# PCB_MINI_FB_ACS_V1.net
KiCad netlist of a schematic drawn in EasyEDA
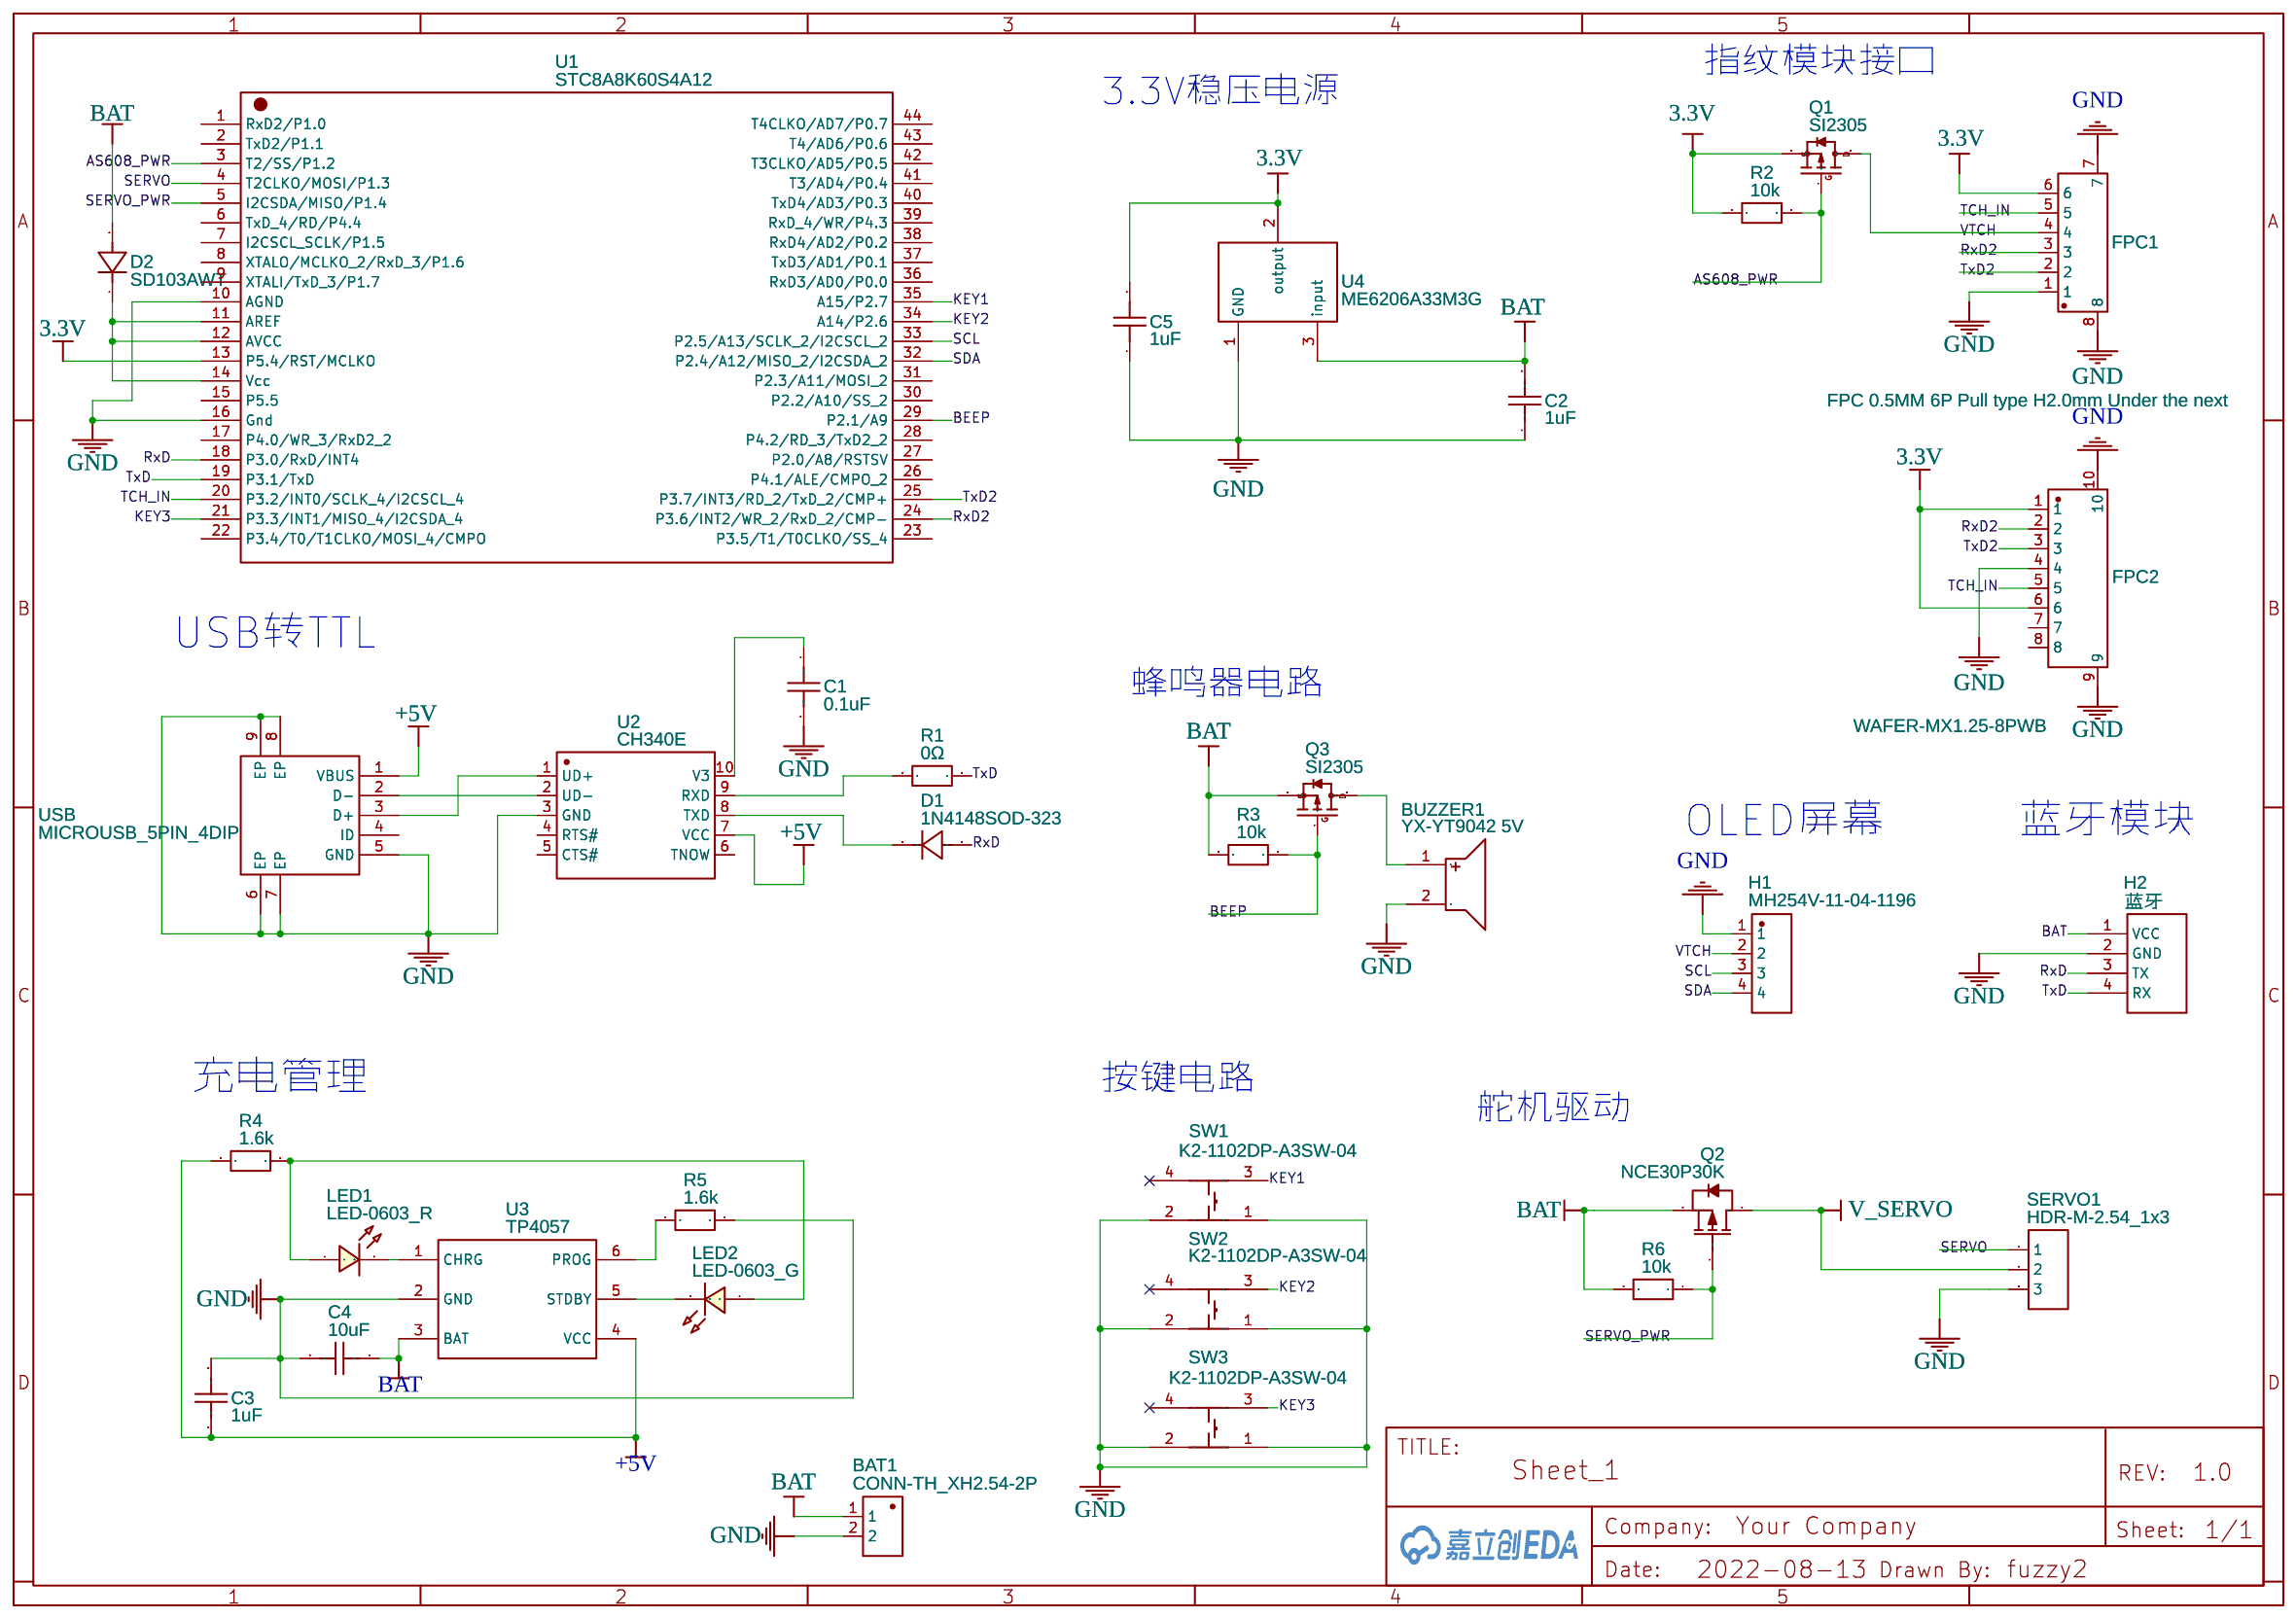
[diagram p0: schematic sheet]

(export (version "E")
  (design (tool "Eeschema 10.0.6"))
  (components
    (comp (ref "BAT1")
      (value "CONN-TH_XH2.54-2P")
      (fields
        (field (name "BOM_Manufacturer Part") "HX25037-2A")
        (field (name "BOM_Supplier Part") "C9900012767")
      )
      (libsource (lib "") (part "CONN-TH_XH2.54-2P"))
    )
    (comp (ref "BUZZER1")
      (value "YX-YT9042 5V")
      (fields
        (field (name "BOM_Manufacturer Part") "YX-YT9042 5v")
        (field (name "BOM_Supplier Part") "C781848")
      )
      (libsource (lib "") (part "YX-YT9042 5V"))
    )
    (comp (ref "C1")
      (value "0.1uF")
      (fields
        (field (name "BOM_Manufacturer Part") "0603BB104K500NGT")
        (field (name "BOM_Supplier Part") "C2168571")
      )
      (libsource (lib "") (part "0603BB104K500NGT"))
    )
    (comp (ref "C2")
      (value "1uF")
      (fields
        (field (name "BOM_Manufacturer Part") "CL10A105KP8NNWC")
        (field (name "BOM_Supplier Part") "C307456")
      )
      (libsource (lib "") (part "CL10A105KP8NNWC"))
    )
    (comp (ref "C3")
      (value "1uF")
      (fields
        (field (name "BOM_Manufacturer Part") "CL10A105KP8NNWC")
        (field (name "BOM_Supplier Part") "C307456")
      )
      (libsource (lib "") (part "CL10A105KP8NNWC"))
    )
    (comp (ref "C4")
      (value "10uF")
      (fields
        (field (name "BOM_Manufacturer Part") "CL10A106MA8NRNC")
        (field (name "BOM_Supplier Part") "C96446")
      )
      (libsource (lib "") (part "CL10A106MA8NRNC"))
    )
    (comp (ref "C5")
      (value "1uF")
      (fields
        (field (name "BOM_Manufacturer Part") "CL10A105KP8NNWC")
        (field (name "BOM_Supplier Part") "C307456")
      )
      (libsource (lib "") (part "CL10A105KP8NNWC"))
    )
    (comp (ref "D1")
      (value "1N4148SOD-323")
      (fields (field (name "BOM_Supplier Part") "C2972761"))
      (libsource (lib "") (part "1N4148SOD-323"))
    )
    (comp (ref "D2")
      (value "SD103AWT")
      (fields (field (name "BOM_Supplier Part") "C840750"))
      (libsource (lib "") (part "SD103AWT"))
    )
    (comp (ref "FPC1")
      (value "FPC 0.5MM 6P Pull type H2.0mm Under the next")
      (fields (field (name "BOM_Supplier Part") "C11048"))
      (libsource (lib "") (part "FPC 0.5MM 6P Pull type H2.0mm Under the next"))
    )
    (comp (ref "FPC2")
      (value "WAFER-MX1.25-8PWB")
      (fields (field (name "BOM_Supplier Part") "C3029365"))
      (libsource (lib "") (part "WAFER-MX1.25-8PWB"))
    )
    (comp (ref "H1")
      (value "MH254V-11-04-1196")
      (fields (field (name "BOM_Supplier Part") "C3015083"))
      (libsource (lib "") (part "MH254V-11-04-1196"))
    )
    (comp (ref "H2")
      (value "蓝牙")
      (fields
        (field (name "BOM_Manufacturer Part") "220S-1*4P H=8.5MM Ytype Gold-plated")
        (field (name "BOM_Supplier Part") "C124413")
      )
      (libsource (lib "") (part "蓝牙"))
    )
    (comp (ref "LED1")
      (value "LED-0603_R")
      (fields
        (field (name "BOM_Manufacturer Part") "19-217/R6C-AL1M2VY/3T")
        (field (name "BOM_Supplier Part") "C72044")
      )
      (libsource (lib "") (part "LED-0603_R"))
    )
    (comp (ref "LED2")
      (value "LED-0603_G")
      (fields
        (field (name "BOM_Manufacturer Part") "19-217/GHC-YR1S2/3T")
        (field (name "BOM_Supplier Part") "C72043")
      )
      (libsource (lib "") (part "LED-0603_G"))
    )
    (comp (ref "Q1")
      (value "SI2305")
      (fields (field (name "BOM_Supplier Part") "C181088"))
      (libsource (lib "") (part "SI2305"))
    )
    (comp (ref "Q2")
      (value "NCE30P30K")
      (fields (field (name "BOM_Supplier Part") "C130106"))
      (libsource (lib "") (part "NCE30P30K"))
    )
    (comp (ref "Q3")
      (value "SI2305")
      (fields (field (name "BOM_Supplier Part") "C181088"))
      (libsource (lib "") (part "SI2305"))
    )
    (comp (ref "R1")
      (value "0Ω")
      (fields
        (field (name "BOM_Manufacturer Part") "CSRF0603FT2L50")
        (field (name "BOM_Supplier Part") "C106974")
      )
      (libsource (lib "") (part "CSRF0603FT2L50"))
    )
    (comp (ref "R2")
      (value "10k")
      (fields
        (field (name "BOM_Manufacturer Part") "0603WAF510KT5E")
        (field (name "BOM_Supplier Part") "C25197")
      )
      (libsource (lib "") (part "R_0603_EU"))
    )
    (comp (ref "R3")
      (value "10k")
      (fields
        (field (name "BOM_Manufacturer Part") "0603WAF510KT5E")
        (field (name "BOM_Supplier Part") "C25197")
      )
      (libsource (lib "") (part "R_0603_EU"))
    )
    (comp (ref "R4")
      (value "1.6k")
      (fields
        (field (name "BOM_Manufacturer Part") "RMC060331.6K1%N")
        (field (name "BOM_Supplier Part") "C325743")
      )
      (libsource (lib "") (part "R_0603_EU"))
    )
    (comp (ref "R5")
      (value "1.6k")
      (fields
        (field (name "BOM_Manufacturer Part") "RMC060331.6K1%N")
        (field (name "BOM_Supplier Part") "C325743")
      )
      (libsource (lib "") (part "R_0603_EU"))
    )
    (comp (ref "R6")
      (value "10k")
      (fields
        (field (name "BOM_Manufacturer Part") "0603WAF510KT5E")
        (field (name "BOM_Supplier Part") "C25197")
      )
      (libsource (lib "") (part "R_0603_EU"))
    )
    (comp (ref "SERVO1")
      (value "HDR-M-2.54_1x3")
      (fields (field (name "BOM_Supplier Part") "C180248"))
      (libsource (lib "") (part "HDR-M-2.54_1x3"))
    )
    (comp (ref "SW1")
      (value "K2-1102DP-A3SW-04")
      (fields (field (name "BOM_Supplier Part") "C136685"))
      (libsource (lib "") (part "K2-1102DP-A3SW-04"))
    )
    (comp (ref "SW2")
      (value "K2-1102DP-A3SW-04")
      (fields (field (name "BOM_Supplier Part") "C136685"))
      (libsource (lib "") (part "K2-1102DP-A3SW-04"))
    )
    (comp (ref "SW3")
      (value "K2-1102DP-A3SW-04")
      (fields (field (name "BOM_Supplier Part") "C136685"))
      (libsource (lib "") (part "K2-1102DP-A3SW-04"))
    )
    (comp (ref "U1")
      (value "STC8A8K60S4A12")
      (fields (field (name "BOM_Supplier Part") "C98240"))
      (libsource (lib "") (part "STC8A8K60S4A12"))
    )
    (comp (ref "U2")
      (value "CH340E")
      (fields (field (name "BOM_Supplier Part") "C99652"))
      (libsource (lib "") (part "CH340E"))
    )
    (comp (ref "U3")
      (value "TP4057")
      (fields (field (name "BOM_Supplier Part") "C12044"))
      (libsource (lib "") (part "TP4057"))
    )
    (comp (ref "U4")
      (value "ME6206A33M3G")
      (fields
        (field (name "BOM_Manufacturer Part") "LN6206P332MR-G")
        (field (name "BOM_Supplier Part") "C141407")
      )
      (libsource (lib "") (part "ME6206A33M3G"))
    )
    (comp (ref "USB")
      (value "MICROUSB_5PIN_4DIP")
      (fields (field (name "BOM_Supplier Part") "C9900010529"))
      (libsource (lib "") (part "MICROUSB_5PIN_4DIP"))
    )
  )
  (nets
    (net (code "1") (name "+5V") (class "Default")
      (node (ref "C3") (pin "1") (pinfunction "1_1") (pintype "unspecified"))
      (node (ref "R4") (pin "2") (pinfunction "2_2") (pintype "unspecified"))
      (node (ref "U2") (pin "7") (pinfunction "VCC_7") (pintype "unspecified"))
      (node (ref "U3") (pin "4") (pinfunction "VCC_4") (pintype "unspecified"))
      (node (ref "USB") (pin "1") (pinfunction "VBUS_1") (pintype "unspecified"))
    )
    (net (code "2") (name "/AS608_PWR") (class "Default")
      (node (ref "Q1") (pin "1") (pinfunction "G_1") (pintype "unspecified"))
      (node (ref "R2") (pin "1") (pinfunction "1_1") (pintype "unspecified"))
      (node (ref "U1") (pin "3") (pinfunction "T2/SS/P1.2_3") (pintype "unspecified"))
    )
    (net (code "3") (name "/BEEP") (class "Default")
      (node (ref "Q3") (pin "1") (pinfunction "G_1") (pintype "unspecified"))
      (node (ref "R3") (pin "1") (pinfunction "1_1") (pintype "unspecified"))
      (node (ref "U1") (pin "29") (pinfunction "P2.1/A9_29") (pintype "unspecified"))
    )
    (net (code "4") (name "/KEY1") (class "Default")
      (node (ref "SW1") (pin "3") (pinfunction "3_3") (pintype "unspecified"))
      (node (ref "U1") (pin "35") (pinfunction "A15/P2.7_35") (pintype "unspecified"))
    )
    (net (code "5") (name "/KEY2") (class "Default")
      (node (ref "SW2") (pin "3") (pinfunction "3_3") (pintype "unspecified"))
      (node (ref "U1") (pin "34") (pinfunction "A14/P2.6_34") (pintype "unspecified"))
    )
    (net (code "6") (name "/KEY3") (class "Default")
      (node (ref "SW3") (pin "3") (pinfunction "3_3") (pintype "unspecified"))
      (node (ref "U1") (pin "21") (pinfunction "P3.3/INT1/MISO_4/I2CSDA_4_21") (pintype "unspecified"))
    )
    (net (code "7") (name "/RxD") (class "Default")
      (node (ref "D1") (pin "2") (pinfunction "A_2") (pintype "unspecified"))
      (node (ref "H2") (pin "3") (pinfunction "TX_3") (pintype "unspecified"))
      (node (ref "U1") (pin "18") (pinfunction "P3.0/RxD/INT4_18") (pintype "unspecified"))
    )
    (net (code "8") (name "/RxD2") (class "Default")
      (node (ref "FPC1") (pin "3") (pinfunction "3_3") (pintype "unspecified"))
      (node (ref "FPC2") (pin "2") (pinfunction "2_2") (pintype "unspecified"))
      (node (ref "U1") (pin "24") (pinfunction "P3.6/INT2/WR_2/RxD_2/CMP-_24") (pintype "unspecified"))
    )
    (net (code "9") (name "/SCL") (class "Default")
      (node (ref "H1") (pin "3") (pinfunction "3_3") (pintype "unspecified"))
      (node (ref "U1") (pin "33") (pinfunction "P2.5/A13/SCLK_2/I2CSCL_2_33") (pintype "unspecified"))
    )
    (net (code "10") (name "/SDA") (class "Default")
      (node (ref "H1") (pin "4") (pinfunction "4_4") (pintype "unspecified"))
      (node (ref "U1") (pin "32") (pinfunction "P2.4/A12/MISO_2/I2CSDA_2_32") (pintype "unspecified"))
    )
    (net (code "11") (name "/SERVO") (class "Default")
      (node (ref "SERVO1") (pin "1") (pinfunction "1_1") (pintype "input"))
      (node (ref "U1") (pin "4") (pinfunction "T2CLKO/MOSI/P1.3_4") (pintype "unspecified"))
    )
    (net (code "12") (name "/SERVO_PWR") (class "Default")
      (node (ref "Q2") (pin "1") (pinfunction "G_1") (pintype "unspecified"))
      (node (ref "R6") (pin "1") (pinfunction "1_1") (pintype "unspecified"))
      (node (ref "U1") (pin "5") (pinfunction "I2CSDA/MISO/P1.4_5") (pintype "unspecified"))
    )
    (net (code "13") (name "/TCH_IN") (class "Default")
      (node (ref "FPC1") (pin "5") (pinfunction "5_5") (pintype "unspecified"))
      (node (ref "FPC2") (pin "5") (pinfunction "5_5") (pintype "unspecified"))
      (node (ref "U1") (pin "20") (pinfunction "P3.2/INT0/SCLK_4/I2CSCL_4_20") (pintype "unspecified"))
    )
    (net (code "14") (name "/TxD") (class "Default")
      (node (ref "H2") (pin "4") (pinfunction "RX_4") (pintype "unspecified"))
      (node (ref "R1") (pin "2") (pinfunction "2_2") (pintype "unspecified"))
      (node (ref "U1") (pin "19") (pinfunction "P3.1/TxD_19") (pintype "unspecified"))
    )
    (net (code "15") (name "/TxD2") (class "Default")
      (node (ref "FPC1") (pin "2") (pinfunction "2_2") (pintype "unspecified"))
      (node (ref "FPC2") (pin "3") (pinfunction "3_3") (pintype "unspecified"))
      (node (ref "U1") (pin "25") (pinfunction "P3.7/INT3/RD_2/TxD_2/CMP+_25") (pintype "unspecified"))
    )
    (net (code "16") (name "/VTCH") (class "Default")
      (node (ref "FPC1") (pin "4") (pinfunction "4_4") (pintype "unspecified"))
      (node (ref "H1") (pin "2") (pinfunction "2_2") (pintype "unspecified"))
      (node (ref "Q1") (pin "3") (pinfunction "D_3") (pintype "unspecified"))
    )
    (net (code "17") (name "3.3V") (class "Default")
      (node (ref "C5") (pin "2") (pinfunction "2_2") (pintype "unspecified"))
      (node (ref "FPC1") (pin "6") (pinfunction "6_6") (pintype "unspecified"))
      (node (ref "FPC2") (pin "1") (pinfunction "1_1") (pintype "unspecified"))
      (node (ref "FPC2") (pin "6") (pinfunction "6_6") (pintype "unspecified"))
      (node (ref "Q1") (pin "2") (pinfunction "S_2") (pintype "unspecified"))
      (node (ref "R2") (pin "2") (pinfunction "2_2") (pintype "unspecified"))
      (node (ref "U1") (pin "13") (pinfunction "P5.4/RST/MCLKO_13") (pintype "unspecified"))
      (node (ref "U4") (pin "2") (pinfunction "output_2") (pintype "unspecified"))
    )
    (net (code "18") (name "BAT") (class "Default")
      (node (ref "BAT1") (pin "1") (pinfunction "1_1") (pintype "unspecified"))
      (node (ref "C2") (pin "2") (pinfunction "2_2") (pintype "unspecified"))
      (node (ref "C4") (pin "2") (pinfunction "2_2") (pintype "unspecified"))
      (node (ref "D2") (pin "2") (pinfunction "A_2") (pintype "unspecified"))
      (node (ref "H2") (pin "1") (pinfunction "VCC_1") (pintype "unspecified"))
      (node (ref "Q2") (pin "3") (pinfunction "S_3") (pintype "unspecified"))
      (node (ref "Q3") (pin "2") (pinfunction "S_2") (pintype "unspecified"))
      (node (ref "R3") (pin "2") (pinfunction "2_2") (pintype "unspecified"))
      (node (ref "R6") (pin "2") (pinfunction "2_2") (pintype "unspecified"))
      (node (ref "U3") (pin "3") (pinfunction "BAT_3") (pintype "unspecified"))
      (node (ref "U4") (pin "3") (pinfunction "input_3") (pintype "unspecified"))
    )
    (net (code "19") (name "GND") (class "Default")
      (node (ref "BAT1") (pin "2") (pinfunction "2_2") (pintype "unspecified"))
      (node (ref "BUZZER1") (pin "2") (pinfunction "2_2") (pintype "unspecified"))
      (node (ref "C1") (pin "2") (pinfunction "2_2") (pintype "unspecified"))
      (node (ref "C2") (pin "1") (pinfunction "1_1") (pintype "unspecified"))
      (node (ref "C3") (pin "2") (pinfunction "2_2") (pintype "unspecified"))
      (node (ref "C4") (pin "1") (pinfunction "1_1") (pintype "unspecified"))
      (node (ref "C5") (pin "1") (pinfunction "1_1") (pintype "unspecified"))
      (node (ref "FPC1") (pin "1") (pinfunction "1_1") (pintype "unspecified"))
      (node (ref "FPC1") (pin "7") (pinfunction "7_7") (pintype "unspecified"))
      (node (ref "FPC1") (pin "8") (pinfunction "8_8") (pintype "unspecified"))
      (node (ref "FPC2") (pin "10") (pinfunction "10_10") (pintype "unspecified"))
      (node (ref "FPC2") (pin "4") (pinfunction "4_4") (pintype "unspecified"))
      (node (ref "FPC2") (pin "9") (pinfunction "9_9") (pintype "unspecified"))
      (node (ref "H1") (pin "1") (pinfunction "1_1") (pintype "unspecified"))
      (node (ref "H2") (pin "2") (pinfunction "GND_2") (pintype "unspecified"))
      (node (ref "R5") (pin "1") (pinfunction "1_1") (pintype "unspecified"))
      (node (ref "SERVO1") (pin "3") (pinfunction "3_3") (pintype "input"))
      (node (ref "SW1") (pin "1") (pinfunction "1_1") (pintype "unspecified"))
      (node (ref "SW1") (pin "2") (pinfunction "2_2") (pintype "unspecified"))
      (node (ref "SW2") (pin "1") (pinfunction "1_1") (pintype "unspecified"))
      (node (ref "SW2") (pin "2") (pinfunction "2_2") (pintype "unspecified"))
      (node (ref "SW3") (pin "1") (pinfunction "1_1") (pintype "unspecified"))
      (node (ref "SW3") (pin "2") (pinfunction "2_2") (pintype "unspecified"))
      (node (ref "U1") (pin "10") (pinfunction "AGND_10") (pintype "unspecified"))
      (node (ref "U1") (pin "16") (pinfunction "Gnd_16") (pintype "unspecified"))
      (node (ref "U2") (pin "3") (pinfunction "GND_3") (pintype "unspecified"))
      (node (ref "U3") (pin "2") (pinfunction "GND_2") (pintype "unspecified"))
      (node (ref "U4") (pin "1") (pinfunction "GND_1") (pintype "unspecified"))
      (node (ref "USB") (pin "5") (pinfunction "GND_5") (pintype "unspecified"))
      (node (ref "USB") (pin "6") (pinfunction "EP_6") (pintype "unspecified"))
      (node (ref "USB") (pin "7") (pinfunction "EP_7") (pintype "unspecified"))
      (node (ref "USB") (pin "8") (pinfunction "EP_8") (pintype "unspecified"))
      (node (ref "USB") (pin "9") (pinfunction "EP_9") (pintype "unspecified"))
    )
    (net (code "20") (name "Net-(D1-K)") (class "Default")
      (node (ref "D1") (pin "1") (pinfunction "K_1") (pintype "unspecified"))
      (node (ref "U2") (pin "8") (pinfunction "TXD_8") (pintype "unspecified"))
    )
    (net (code "21") (name "Net-(D2-K)") (class "Default")
      (node (ref "D2") (pin "1") (pinfunction "K_1") (pintype "unspecified"))
      (node (ref "U1") (pin "11") (pinfunction "AREF_11") (pintype "unspecified"))
      (node (ref "U1") (pin "12") (pinfunction "AVCC_12") (pintype "unspecified"))
      (node (ref "U1") (pin "14") (pinfunction "Vcc_14") (pintype "unspecified"))
    )
    (net (code "22") (name "Net-(LED1-Pad1)") (class "Default")
      (node (ref "LED1") (pin "1") (pinfunction "1_1") (pintype "unspecified"))
      (node (ref "LED2") (pin "1") (pinfunction "1_1") (pintype "unspecified"))
      (node (ref "R4") (pin "1") (pinfunction "1_1") (pintype "unspecified"))
    )
    (net (code "23") (name "Net-(Q3-D)") (class "Default")
      (node (ref "BUZZER1") (pin "1") (pinfunction "1_1") (pintype "unspecified"))
      (node (ref "Q3") (pin "3") (pinfunction "D_3") (pintype "unspecified"))
    )
    (net (code "24") (name "Net-(U2-RXD)") (class "Default")
      (node (ref "R1") (pin "1") (pinfunction "1_1") (pintype "unspecified"))
      (node (ref "U2") (pin "9") (pinfunction "RXD_9") (pintype "unspecified"))
    )
    (net (code "25") (name "Net-(U2-UD+)") (class "Default")
      (node (ref "U2") (pin "1") (pinfunction "UD+_1") (pintype "unspecified"))
      (node (ref "USB") (pin "3") (pinfunction "D+_3") (pintype "unspecified"))
    )
    (net (code "26") (name "Net-(U2-UD-)") (class "Default")
      (node (ref "U2") (pin "2") (pinfunction "UD-_2") (pintype "unspecified"))
      (node (ref "USB") (pin "2") (pinfunction "D-_2") (pintype "unspecified"))
    )
    (net (code "27") (name "Net-(U2-V3)") (class "Default")
      (node (ref "C1") (pin "1") (pinfunction "1_1") (pintype "unspecified"))
      (node (ref "U2") (pin "10") (pinfunction "V3_10") (pintype "unspecified"))
    )
    (net (code "28") (name "Net-(U3-CHRG)") (class "Default")
      (node (ref "LED1") (pin "2") (pinfunction "2_2") (pintype "unspecified"))
      (node (ref "U3") (pin "1") (pinfunction "CHRG_1") (pintype "unspecified"))
    )
    (net (code "29") (name "Net-(U3-PROG)") (class "Default")
      (node (ref "R5") (pin "2") (pinfunction "2_2") (pintype "unspecified"))
      (node (ref "U3") (pin "6") (pinfunction "PROG_6") (pintype "unspecified"))
    )
    (net (code "30") (name "Net-(U3-STDBY)") (class "Default")
      (node (ref "LED2") (pin "2") (pinfunction "2_2") (pintype "unspecified"))
      (node (ref "U3") (pin "5") (pinfunction "STDBY_5") (pintype "unspecified"))
    )
    (net (code "31") (name "V_SERVO") (class "Default")
      (node (ref "Q2") (pin "2") (pinfunction "D_2") (pintype "unspecified"))
      (node (ref "SERVO1") (pin "2") (pinfunction "2_2") (pintype "input"))
    )
    (net (code "32") (name "unconnected-(FPC2-Pad7)") (class "Default")
      (node (ref "FPC2") (pin "7") (pinfunction "7_7") (pintype "unspecified"))
    )
    (net (code "33") (name "unconnected-(FPC2-Pad8)") (class "Default")
      (node (ref "FPC2") (pin "8") (pinfunction "8_8") (pintype "unspecified"))
    )
    (net (code "34") (name "unconnected-(SW1-Pad4)") (class "Default")
      (node (ref "SW1") (pin "4") (pinfunction "4_4") (pintype "unspecified+no_connect"))
    )
    (net (code "35") (name "unconnected-(SW2-Pad4)") (class "Default")
      (node (ref "SW2") (pin "4") (pinfunction "4_4") (pintype "unspecified+no_connect"))
    )
    (net (code "36") (name "unconnected-(SW3-Pad4)") (class "Default")
      (node (ref "SW3") (pin "4") (pinfunction "4_4") (pintype "unspecified+no_connect"))
    )
    (net (code "37") (name "unconnected-(U1-I2CSCL_SCLK{slash}P1.5-Pad7)") (class "Default")
      (node (ref "U1") (pin "7") (pinfunction "I2CSCL_SCLK/P1.5_7") (pintype "unspecified"))
    )
    (net (code "38") (name "unconnected-(U1-P2.0{slash}A8{slash}RSTSV-Pad27)") (class "Default")
      (node (ref "U1") (pin "27") (pinfunction "P2.0/A8/RSTSV_27") (pintype "unspecified"))
    )
    (net (code "39") (name "unconnected-(U1-P2.2{slash}A10{slash}SS_2-Pad30)") (class "Default")
      (node (ref "U1") (pin "30") (pinfunction "P2.2/A10/SS_2_30") (pintype "unspecified"))
    )
    (net (code "40") (name "unconnected-(U1-P2.3{slash}A11{slash}MOSI_2-Pad31)") (class "Default")
      (node (ref "U1") (pin "31") (pinfunction "P2.3/A11/MOSI_2_31") (pintype "unspecified"))
    )
    (net (code "41") (name "unconnected-(U1-P3.4{slash}T0{slash}T1CLKO{slash}MOSI_4{slash}CMPO-Pad22)") (class "Default")
      (node (ref "U1") (pin "22") (pinfunction "P3.4/T0/T1CLKO/MOSI_4/CMPO_22") (pintype "unspecified"))
    )
    (net (code "42") (name "unconnected-(U1-P3.5{slash}T1{slash}T0CLKO{slash}SS_4-Pad23)") (class "Default")
      (node (ref "U1") (pin "23") (pinfunction "P3.5/T1/T0CLKO/SS_4_23") (pintype "unspecified"))
    )
    (net (code "43") (name "unconnected-(U1-P4.0{slash}WR_3{slash}RxD2_2-Pad17)") (class "Default")
      (node (ref "U1") (pin "17") (pinfunction "P4.0/WR_3/RxD2_2_17") (pintype "unspecified"))
    )
    (net (code "44") (name "unconnected-(U1-P4.1{slash}ALE{slash}CMPO_2-Pad26)") (class "Default")
      (node (ref "U1") (pin "26") (pinfunction "P4.1/ALE/CMPO_2_26") (pintype "unspecified"))
    )
    (net (code "45") (name "unconnected-(U1-P4.2{slash}RD_3{slash}TxD2_2-Pad28)") (class "Default")
      (node (ref "U1") (pin "28") (pinfunction "P4.2/RD_3/TxD2_2_28") (pintype "unspecified"))
    )
    (net (code "46") (name "unconnected-(U1-P5.5-Pad15)") (class "Default")
      (node (ref "U1") (pin "15") (pinfunction "P5.5_15") (pintype "unspecified"))
    )
    (net (code "47") (name "unconnected-(U1-RxD2{slash}P1.0-Pad1)") (class "Default")
      (node (ref "U1") (pin "1") (pinfunction "RxD2/P1.0_1") (pintype "unspecified"))
    )
    (net (code "48") (name "unconnected-(U1-RxD3{slash}AD0{slash}P0.0-Pad36)") (class "Default")
      (node (ref "U1") (pin "36") (pinfunction "RxD3/AD0/P0.0_36") (pintype "unspecified"))
    )
    (net (code "49") (name "unconnected-(U1-RxD4{slash}AD2{slash}P0.2-Pad38)") (class "Default")
      (node (ref "U1") (pin "38") (pinfunction "RxD4/AD2/P0.2_38") (pintype "unspecified"))
    )
    (net (code "50") (name "unconnected-(U1-RxD_4{slash}WR{slash}P4.3-Pad39)") (class "Default")
      (node (ref "U1") (pin "39") (pinfunction "RxD_4/WR/P4.3_39") (pintype "unspecified"))
    )
    (net (code "51") (name "unconnected-(U1-T3CLKO{slash}AD5{slash}P0.5-Pad42)") (class "Default")
      (node (ref "U1") (pin "42") (pinfunction "T3CLKO/AD5/P0.5_42") (pintype "unspecified"))
    )
    (net (code "52") (name "unconnected-(U1-T3{slash}AD4{slash}P0.4-Pad41)") (class "Default")
      (node (ref "U1") (pin "41") (pinfunction "T3/AD4/P0.4_41") (pintype "unspecified"))
    )
    (net (code "53") (name "unconnected-(U1-T4CLKO{slash}AD7{slash}P0.7-Pad44)") (class "Default")
      (node (ref "U1") (pin "44") (pinfunction "T4CLKO/AD7/P0.7_44") (pintype "unspecified"))
    )
    (net (code "54") (name "unconnected-(U1-T4{slash}AD6{slash}P0.6-Pad43)") (class "Default")
      (node (ref "U1") (pin "43") (pinfunction "T4/AD6/P0.6_43") (pintype "unspecified"))
    )
    (net (code "55") (name "unconnected-(U1-TxD2{slash}P1.1-Pad2)") (class "Default")
      (node (ref "U1") (pin "2") (pinfunction "TxD2/P1.1_2") (pintype "unspecified"))
    )
    (net (code "56") (name "unconnected-(U1-TxD3{slash}AD1{slash}P0.1-Pad37)") (class "Default")
      (node (ref "U1") (pin "37") (pinfunction "TxD3/AD1/P0.1_37") (pintype "unspecified"))
    )
    (net (code "57") (name "unconnected-(U1-TxD4{slash}AD3{slash}P0.3-Pad40)") (class "Default")
      (node (ref "U1") (pin "40") (pinfunction "TxD4/AD3/P0.3_40") (pintype "unspecified"))
    )
    (net (code "58") (name "unconnected-(U1-TxD_4{slash}RD{slash}P4.4-Pad6)") (class "Default")
      (node (ref "U1") (pin "6") (pinfunction "TxD_4/RD/P4.4_6") (pintype "unspecified"))
    )
    (net (code "59") (name "unconnected-(U1-XTALI{slash}TxD_3{slash}P1.7-Pad9)") (class "Default")
      (node (ref "U1") (pin "9") (pinfunction "XTALI/TxD_3/P1.7_9") (pintype "unspecified"))
    )
    (net (code "60") (name "unconnected-(U1-XTALO{slash}MCLKO_2{slash}RxD_3{slash}P1.6-Pad8)") (class "Default")
      (node (ref "U1") (pin "8") (pinfunction "XTALO/MCLKO_2/RxD_3/P1.6_8") (pintype "unspecified"))
    )
    (net (code "61") (name "unconnected-(U2-CTS#-Pad5)") (class "Default")
      (node (ref "U2") (pin "5") (pinfunction "CTS#_5") (pintype "unspecified"))
    )
    (net (code "62") (name "unconnected-(U2-RTS#-Pad4)") (class "Default")
      (node (ref "U2") (pin "4") (pinfunction "RTS#_4") (pintype "unspecified"))
    )
    (net (code "63") (name "unconnected-(U2-TNOW-Pad6)") (class "Default")
      (node (ref "U2") (pin "6") (pinfunction "TNOW_6") (pintype "unspecified"))
    )
    (net (code "64") (name "unconnected-(USB-ID-Pad4)") (class "Default")
      (node (ref "USB") (pin "4") (pinfunction "ID_4") (pintype "unspecified"))
    )
  )
)
